# SerialKey.net
KiCad netlist of a schematic drawn in EAGLE
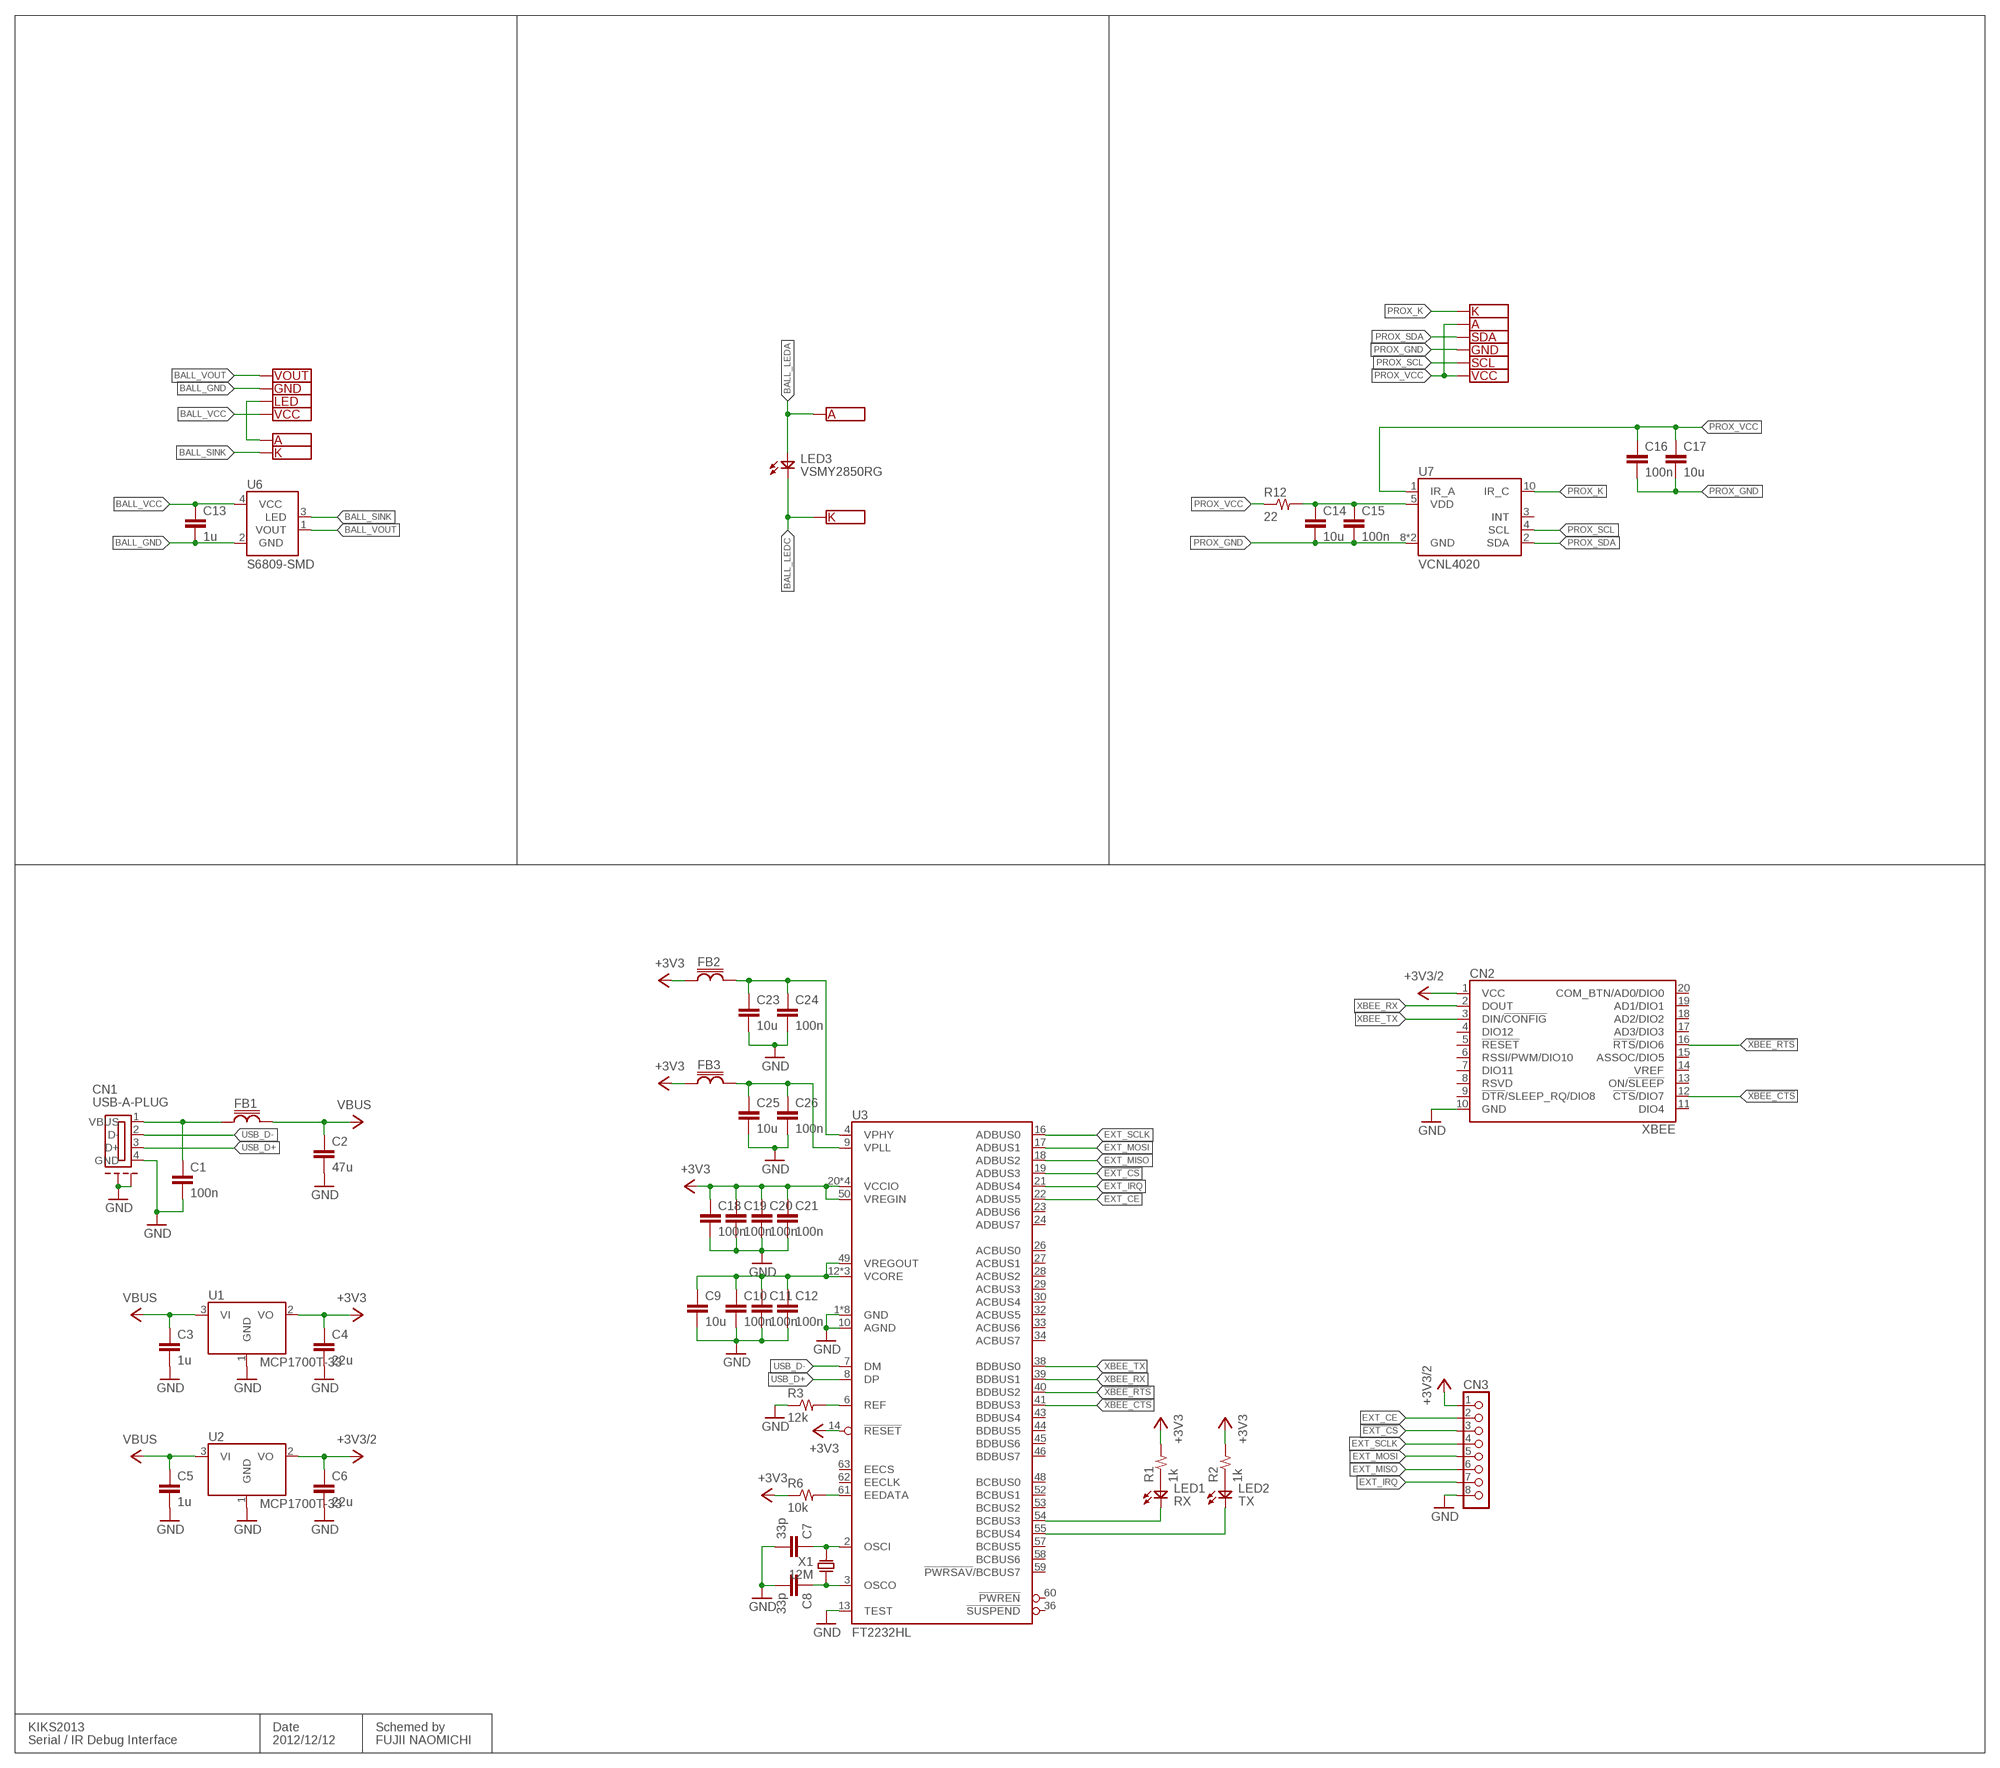
[diagram p0: schematic, sheet 1]

(export (version "E")
  (design (tool "Eeschema 10.0.6"))
  (components
    (comp (ref "C1")
      (value "100n")
      (footprint "eagle-import:1005")
      (libsource (lib "eagle-import") (part "C1005"))
    )
    (comp (ref "C2")
      (value "47u")
      (footprint "eagle-import:3216")
      (libsource (lib "eagle-import") (part "C3216"))
    )
    (comp (ref "C3")
      (value "1u")
      (footprint "eagle-import:1005")
      (libsource (lib "eagle-import") (part "C1005"))
    )
    (comp (ref "C4")
      (value "22u")
      (footprint "eagle-import:2012")
      (libsource (lib "eagle-import") (part "C2012"))
    )
    (comp (ref "C5")
      (value "1u")
      (footprint "eagle-import:1005")
      (libsource (lib "eagle-import") (part "C1005"))
    )
    (comp (ref "C6")
      (value "22u")
      (footprint "eagle-import:2012")
      (libsource (lib "eagle-import") (part "C2012"))
    )
    (comp (ref "C7")
      (value "33p")
      (footprint "eagle-import:1608")
      (libsource (lib "eagle-import") (part "C1608"))
    )
    (comp (ref "C8")
      (value "33p")
      (footprint "eagle-import:1608")
      (libsource (lib "eagle-import") (part "C1608"))
    )
    (comp (ref "C9")
      (value "10u")
      (footprint "eagle-import:1608")
      (libsource (lib "eagle-import") (part "C1608"))
    )
    (comp (ref "C10")
      (value "100n")
      (footprint "eagle-import:1005")
      (libsource (lib "eagle-import") (part "C1005"))
    )
    (comp (ref "C11")
      (value "100n")
      (footprint "eagle-import:1005")
      (libsource (lib "eagle-import") (part "C1005"))
    )
    (comp (ref "C12")
      (value "100n")
      (footprint "eagle-import:1005")
      (libsource (lib "eagle-import") (part "C1005"))
    )
    (comp (ref "C13")
      (value "1u")
      (footprint "eagle-import:1005")
      (libsource (lib "eagle-import") (part "C1005"))
    )
    (comp (ref "C14")
      (value "10u")
      (footprint "eagle-import:1608")
      (libsource (lib "eagle-import") (part "C1608"))
    )
    (comp (ref "C15")
      (value "100n")
      (footprint "eagle-import:1005")
      (libsource (lib "eagle-import") (part "C1005"))
    )
    (comp (ref "C16")
      (value "100n")
      (footprint "eagle-import:1005")
      (libsource (lib "eagle-import") (part "C1005"))
    )
    (comp (ref "C17")
      (value "10u")
      (footprint "eagle-import:1608")
      (libsource (lib "eagle-import") (part "C1608"))
    )
    (comp (ref "C18")
      (value "100n")
      (footprint "eagle-import:1005")
      (libsource (lib "eagle-import") (part "C1005"))
    )
    (comp (ref "C19")
      (value "100n")
      (footprint "eagle-import:1005")
      (libsource (lib "eagle-import") (part "C1005"))
    )
    (comp (ref "C20")
      (value "100n")
      (footprint "eagle-import:1005")
      (libsource (lib "eagle-import") (part "C1005"))
    )
    (comp (ref "C21")
      (value "100n")
      (footprint "eagle-import:1005")
      (libsource (lib "eagle-import") (part "C1005"))
    )
    (comp (ref "C23")
      (value "10u")
      (footprint "eagle-import:1608")
      (libsource (lib "eagle-import") (part "C1608"))
    )
    (comp (ref "C24")
      (value "100n")
      (footprint "eagle-import:1005")
      (libsource (lib "eagle-import") (part "C1005"))
    )
    (comp (ref "C25")
      (value "10u")
      (footprint "eagle-import:1608")
      (libsource (lib "eagle-import") (part "C1608"))
    )
    (comp (ref "C26")
      (value "100n")
      (footprint "eagle-import:1005")
      (libsource (lib "eagle-import") (part "C1005"))
    )
    (comp (ref "CN1")
      (value "USB-A-PLUG")
      (footprint "eagle-import:USB-A-PLUG")
      (libsource (lib "eagle-import") (part "USB-A-PLUG"))
    )
    (comp (ref "CN2")
      (value "XBEE")
      (footprint "eagle-import:XBEE-TH-NOSILK")
      (libsource (lib "eagle-import") (part "XBEE-TH-NOSILK"))
    )
    (comp (ref "CN3")
      (value "PIN1X8")
      (footprint "eagle-import:PIN1X8")
      (libsource (lib "eagle-import") (part "PIN1X8"))
    )
    (comp (ref "FB1")
      (value "FB1608")
      (footprint "eagle-import:1608")
      (libsource (lib "eagle-import") (part "FB1608"))
    )
    (comp (ref "FB2")
      (value "FB1608")
      (footprint "eagle-import:1608")
      (libsource (lib "eagle-import") (part "FB1608"))
    )
    (comp (ref "FB3")
      (value "FB1608")
      (footprint "eagle-import:1608")
      (libsource (lib "eagle-import") (part "FB1608"))
    )
    (comp (ref "LED1")
      (value "RX")
      (footprint "eagle-import:1608")
      (libsource (lib "eagle-import") (part "LED1608"))
    )
    (comp (ref "LED2")
      (value "TX")
      (footprint "eagle-import:1608")
      (libsource (lib "eagle-import") (part "LED1608"))
    )
    (comp (ref "LED3")
      (value "VSMY2850RG")
      (footprint "eagle-import:VISHAY-RGW")
      (libsource (lib "eagle-import") (part "VSMY2850RG"))
    )
    (comp (ref "R1")
      (value "1k")
      (footprint "eagle-import:1005")
      (libsource (lib "eagle-import") (part "R1005"))
    )
    (comp (ref "R2")
      (value "1k")
      (footprint "eagle-import:1005")
      (libsource (lib "eagle-import") (part "R1005"))
    )
    (comp (ref "R3")
      (value "12k")
      (footprint "eagle-import:1608")
      (libsource (lib "eagle-import") (part "R1608"))
    )
    (comp (ref "R6")
      (value "10k")
      (footprint "eagle-import:1005")
      (libsource (lib "eagle-import") (part "R1005"))
    )
    (comp (ref "R12")
      (value "22")
      (footprint "eagle-import:1005")
      (libsource (lib "eagle-import") (part "R1005"))
    )
    (comp (ref "T1")
      (value "VOUT")
      (footprint "eagle-import:TERMINAL")
      (libsource (lib "eagle-import") (part "TERMINAL"))
    )
    (comp (ref "T2")
      (value "GND")
      (footprint "eagle-import:TERMINAL")
      (libsource (lib "eagle-import") (part "TERMINAL"))
    )
    (comp (ref "T3")
      (value "LED")
      (footprint "eagle-import:TERMINAL")
      (libsource (lib "eagle-import") (part "TERMINAL"))
    )
    (comp (ref "T4")
      (value "VCC")
      (footprint "eagle-import:TERMINAL")
      (libsource (lib "eagle-import") (part "TERMINAL"))
    )
    (comp (ref "T5")
      (value "A")
      (footprint "eagle-import:TERMINAL")
      (libsource (lib "eagle-import") (part "TERMINAL"))
    )
    (comp (ref "T6")
      (value "K")
      (footprint "eagle-import:TERMINAL")
      (libsource (lib "eagle-import") (part "TERMINAL"))
    )
    (comp (ref "T7")
      (value "A")
      (footprint "eagle-import:TERMINAL")
      (libsource (lib "eagle-import") (part "TERMINAL"))
    )
    (comp (ref "T8")
      (value "K")
      (footprint "eagle-import:TERMINAL")
      (libsource (lib "eagle-import") (part "TERMINAL"))
    )
    (comp (ref "T9")
      (value "SDA")
      (footprint "eagle-import:TERMINAL")
      (libsource (lib "eagle-import") (part "TERMINAL"))
    )
    (comp (ref "T10")
      (value "GND")
      (footprint "eagle-import:TERMINAL")
      (libsource (lib "eagle-import") (part "TERMINAL"))
    )
    (comp (ref "T11")
      (value "SCL")
      (footprint "eagle-import:TERMINAL")
      (libsource (lib "eagle-import") (part "TERMINAL"))
    )
    (comp (ref "T12")
      (value "VCC")
      (footprint "eagle-import:TERMINAL")
      (libsource (lib "eagle-import") (part "TERMINAL"))
    )
    (comp (ref "T13")
      (value "A")
      (footprint "eagle-import:TERMINAL")
      (libsource (lib "eagle-import") (part "TERMINAL"))
    )
    (comp (ref "T14")
      (value "K")
      (footprint "eagle-import:TERMINAL")
      (libsource (lib "eagle-import") (part "TERMINAL"))
    )
    (comp (ref "U1")
      (value "MCP1700T-33")
      (footprint "eagle-import:SOT23-3")
      (libsource (lib "eagle-import") (part "MCP1700T-33"))
    )
    (comp (ref "U2")
      (value "MCP1700T-33")
      (footprint "eagle-import:SOT23-3")
      (libsource (lib "eagle-import") (part "MCP1700T-33"))
    )
    (comp (ref "U3")
      (value "FT2232HL")
      (footprint "eagle-import:QFP64-0.5")
      (libsource (lib "eagle-import") (part "FT2232HL"))
    )
    (comp (ref "U6")
      (value "S6809-SMD")
      (footprint "eagle-import:S6809")
      (libsource (lib "eagle-import") (part "S6809-SMD"))
    )
    (comp (ref "U7")
      (value "VCNL4020")
      (footprint "eagle-import:VCNL4020")
      (libsource (lib "eagle-import") (part "VCNL4020"))
    )
    (comp (ref "X1")
      (value "12M")
      (footprint "eagle-import:HC49")
      (libsource (lib "eagle-import") (part "HC49"))
    )
  )
  (nets
    (net (code "1") (name "+3V3") (class "Default")
      (node (ref "C18") (pin "1") (pinfunction "1_1") (pintype "passive"))
      (node (ref "C19") (pin "1") (pinfunction "1_1") (pintype "passive"))
      (node (ref "C20") (pin "1") (pinfunction "1_1") (pintype "passive"))
      (node (ref "C21") (pin "1") (pinfunction "1_1") (pintype "passive"))
      (node (ref "C4") (pin "1") (pinfunction "1_1") (pintype "passive"))
      (node (ref "FB2") (pin "1") (pinfunction "1_1") (pintype "passive"))
      (node (ref "FB3") (pin "1") (pinfunction "1_1") (pintype "passive"))
      (node (ref "R1") (pin "2") (pinfunction "2_2") (pintype "passive"))
      (node (ref "R2") (pin "2") (pinfunction "2_2") (pintype "passive"))
      (node (ref "R6") (pin "1") (pinfunction "1_1") (pintype "passive"))
      (node (ref "U1") (pin "2") (pinfunction "VO_2") (pintype "bidirectional"))
      (node (ref "U3") (pin "14") (pinfunction "~{RESET}_14") (pintype "bidirectional"))
      (node (ref "U3") (pin "20") (pinfunction "VCCIO_20") (pintype "bidirectional"))
      (node (ref "U3") (pin "31") (pinfunction "VCCIO_31") (pintype "bidirectional"))
      (node (ref "U3") (pin "42") (pinfunction "VCCIO_42") (pintype "bidirectional"))
      (node (ref "U3") (pin "50") (pinfunction "VREGIN_50") (pintype "bidirectional"))
      (node (ref "U3") (pin "56") (pinfunction "VCCIO_56") (pintype "bidirectional"))
    )
    (net (code "2") (name "+3V3{slash}2") (class "Default")
      (node (ref "C6") (pin "1") (pinfunction "1_1") (pintype "passive"))
      (node (ref "CN2") (pin "1") (pinfunction "VCC_1") (pintype "bidirectional"))
      (node (ref "CN3") (pin "1") (pinfunction "1_1") (pintype "passive"))
      (node (ref "U2") (pin "2") (pinfunction "VO_2") (pintype "bidirectional"))
    )
    (net (code "3") (name "/~{EXT_CS}") (class "Default")
      (node (ref "CN3") (pin "3") (pinfunction "3_3") (pintype "passive"))
      (node (ref "U3") (pin "19") (pinfunction "ADBUS3_19") (pintype "bidirectional"))
    )
    (net (code "4") (name "/~{XBEE_CTS}") (class "Default")
      (node (ref "CN2") (pin "12") (pinfunction "~{CTS}/DIO7_12") (pintype "bidirectional"))
      (node (ref "U3") (pin "41") (pinfunction "BDBUS3_41") (pintype "bidirectional"))
    )
    (net (code "5") (name "/~{XBEE_RTS}") (class "Default")
      (node (ref "CN2") (pin "16") (pinfunction "~{RTS}/DIO6_16") (pintype "bidirectional"))
      (node (ref "U3") (pin "40") (pinfunction "BDBUS2_40") (pintype "bidirectional"))
    )
    (net (code "6") (name "BALL_GND") (class "Default")
      (node (ref "C13") (pin "2") (pinfunction "2_2") (pintype "passive"))
      (node (ref "T2") (pin "1") (pinfunction "1_1") (pintype "passive"))
      (node (ref "U6") (pin "2") (pinfunction "GND_2") (pintype "bidirectional"))
    )
    (net (code "7") (name "BALL_LEDA") (class "Default")
      (node (ref "LED3") (pin "A") (pinfunction "A_A") (pintype "passive"))
      (node (ref "T7") (pin "1") (pinfunction "1_1") (pintype "passive"))
    )
    (net (code "8") (name "BALL_LEDC") (class "Default")
      (node (ref "LED3") (pin "K") (pinfunction "K_K") (pintype "passive"))
      (node (ref "T8") (pin "1") (pinfunction "1_1") (pintype "passive"))
    )
    (net (code "9") (name "BALL_SINK") (class "Default")
      (node (ref "T6") (pin "1") (pinfunction "1_1") (pintype "passive"))
      (node (ref "U6") (pin "3") (pinfunction "LED_3") (pintype "bidirectional"))
    )
    (net (code "10") (name "BALL_VCC") (class "Default")
      (node (ref "C13") (pin "1") (pinfunction "1_1") (pintype "passive"))
      (node (ref "T4") (pin "1") (pinfunction "1_1") (pintype "passive"))
      (node (ref "U6") (pin "4") (pinfunction "VCC_4") (pintype "bidirectional"))
    )
    (net (code "11") (name "BALL_VOUT") (class "Default")
      (node (ref "T1") (pin "1") (pinfunction "1_1") (pintype "passive"))
      (node (ref "U6") (pin "1") (pinfunction "VOUT_1") (pintype "bidirectional"))
    )
    (net (code "12") (name "EXT_CE") (class "Default")
      (node (ref "CN3") (pin "2") (pinfunction "2_2") (pintype "passive"))
      (node (ref "U3") (pin "22") (pinfunction "ADBUS5_22") (pintype "bidirectional"))
    )
    (net (code "13") (name "EXT_IRQ") (class "Default")
      (node (ref "CN3") (pin "7") (pinfunction "7_7") (pintype "passive"))
      (node (ref "U3") (pin "21") (pinfunction "ADBUS4_21") (pintype "bidirectional"))
    )
    (net (code "14") (name "EXT_MISO") (class "Default")
      (node (ref "CN3") (pin "6") (pinfunction "6_6") (pintype "passive"))
      (node (ref "U3") (pin "18") (pinfunction "ADBUS2_18") (pintype "bidirectional"))
    )
    (net (code "15") (name "EXT_MOSI") (class "Default")
      (node (ref "CN3") (pin "5") (pinfunction "5_5") (pintype "passive"))
      (node (ref "U3") (pin "17") (pinfunction "ADBUS1_17") (pintype "bidirectional"))
    )
    (net (code "16") (name "EXT_SCLK") (class "Default")
      (node (ref "CN3") (pin "4") (pinfunction "4_4") (pintype "passive"))
      (node (ref "U3") (pin "16") (pinfunction "ADBUS0_16") (pintype "bidirectional"))
    )
    (net (code "17") (name "GND") (class "Default")
      (node (ref "C1") (pin "2") (pinfunction "2_2") (pintype "passive"))
      (node (ref "C10") (pin "2") (pinfunction "2_2") (pintype "passive"))
      (node (ref "C11") (pin "2") (pinfunction "2_2") (pintype "passive"))
      (node (ref "C12") (pin "2") (pinfunction "2_2") (pintype "passive"))
      (node (ref "C18") (pin "2") (pinfunction "2_2") (pintype "passive"))
      (node (ref "C19") (pin "2") (pinfunction "2_2") (pintype "passive"))
      (node (ref "C2") (pin "2") (pinfunction "2_2") (pintype "passive"))
      (node (ref "C20") (pin "2") (pinfunction "2_2") (pintype "passive"))
      (node (ref "C21") (pin "2") (pinfunction "2_2") (pintype "passive"))
      (node (ref "C23") (pin "2") (pinfunction "2_2") (pintype "passive"))
      (node (ref "C24") (pin "2") (pinfunction "2_2") (pintype "passive"))
      (node (ref "C25") (pin "2") (pinfunction "2_2") (pintype "passive"))
      (node (ref "C26") (pin "2") (pinfunction "2_2") (pintype "passive"))
      (node (ref "C3") (pin "2") (pinfunction "2_2") (pintype "passive"))
      (node (ref "C4") (pin "2") (pinfunction "2_2") (pintype "passive"))
      (node (ref "C5") (pin "2") (pinfunction "2_2") (pintype "passive"))
      (node (ref "C6") (pin "2") (pinfunction "2_2") (pintype "passive"))
      (node (ref "C7") (pin "2") (pinfunction "2_2") (pintype "passive"))
      (node (ref "C8") (pin "2") (pinfunction "2_2") (pintype "passive"))
      (node (ref "C9") (pin "2") (pinfunction "2_2") (pintype "passive"))
      (node (ref "CN1") (pin "4") (pinfunction "GND_4") (pintype "passive"))
      (node (ref "CN1") (pin "S1") (pinfunction "S1_S1") (pintype "passive"))
      (node (ref "CN1") (pin "S2") (pinfunction "S2_S2") (pintype "passive"))
      (node (ref "CN2") (pin "10") (pinfunction "GND_10") (pintype "bidirectional"))
      (node (ref "CN3") (pin "8") (pinfunction "8_8") (pintype "passive"))
      (node (ref "R3") (pin "1") (pinfunction "1_1") (pintype "passive"))
      (node (ref "U1") (pin "1") (pinfunction "GND_1") (pintype "bidirectional"))
      (node (ref "U2") (pin "1") (pinfunction "GND_1") (pintype "bidirectional"))
      (node (ref "U3") (pin "1") (pinfunction "GND_1") (pintype "bidirectional"))
      (node (ref "U3") (pin "10") (pinfunction "AGND_10") (pintype "bidirectional"))
      (node (ref "U3") (pin "11") (pinfunction "GND_11") (pintype "bidirectional"))
      (node (ref "U3") (pin "13") (pinfunction "TEST_13") (pintype "bidirectional"))
      (node (ref "U3") (pin "15") (pinfunction "GND_15") (pintype "bidirectional"))
      (node (ref "U3") (pin "25") (pinfunction "GND_25") (pintype "bidirectional"))
      (node (ref "U3") (pin "35") (pinfunction "GND_35") (pintype "bidirectional"))
      (node (ref "U3") (pin "47") (pinfunction "GND_47") (pintype "bidirectional"))
      (node (ref "U3") (pin "5") (pinfunction "GND_5") (pintype "bidirectional"))
      (node (ref "U3") (pin "51") (pinfunction "GND_51") (pintype "bidirectional"))
    )
    (net (code "18") (name "Net-(CN1-VBUS)") (class "Default")
      (node (ref "C1") (pin "1") (pinfunction "1_1") (pintype "passive"))
      (node (ref "CN1") (pin "1") (pinfunction "VBUS_1") (pintype "passive"))
      (node (ref "FB1") (pin "1") (pinfunction "1_1") (pintype "passive"))
    )
    (net (code "19") (name "Net-(LED1-PadA)") (class "Default")
      (node (ref "LED1") (pin "A") (pinfunction "A_A") (pintype "passive"))
      (node (ref "R1") (pin "1") (pinfunction "1_1") (pintype "passive"))
    )
    (net (code "20") (name "Net-(LED2-PadA)") (class "Default")
      (node (ref "LED2") (pin "A") (pinfunction "A_A") (pintype "passive"))
      (node (ref "R2") (pin "1") (pinfunction "1_1") (pintype "passive"))
    )
    (net (code "21") (name "Net-(T3-Pad1)") (class "Default")
      (node (ref "T3") (pin "1") (pinfunction "1_1") (pintype "passive"))
      (node (ref "T5") (pin "1") (pinfunction "1_1") (pintype "passive"))
    )
    (net (code "22") (name "Net-(U3-BCBUS3)") (class "Default")
      (node (ref "LED1") (pin "K") (pinfunction "K_K") (pintype "passive"))
      (node (ref "U3") (pin "54") (pinfunction "BCBUS3_54") (pintype "bidirectional"))
    )
    (net (code "23") (name "Net-(U3-BCBUS4)") (class "Default")
      (node (ref "LED2") (pin "K") (pinfunction "K_K") (pintype "passive"))
      (node (ref "U3") (pin "55") (pinfunction "BCBUS4_55") (pintype "bidirectional"))
    )
    (net (code "24") (name "Net-(U3-EEDATA)") (class "Default")
      (node (ref "R6") (pin "2") (pinfunction "2_2") (pintype "passive"))
      (node (ref "U3") (pin "61") (pinfunction "EEDATA_61") (pintype "bidirectional"))
    )
    (net (code "25") (name "Net-(U3-OSCI)") (class "Default")
      (node (ref "C7") (pin "1") (pinfunction "1_1") (pintype "passive"))
      (node (ref "U3") (pin "2") (pinfunction "OSCI_2") (pintype "bidirectional"))
      (node (ref "X1") (pin "1") (pinfunction "A_1") (pintype "passive"))
    )
    (net (code "26") (name "Net-(U3-OSCO)") (class "Default")
      (node (ref "C8") (pin "1") (pinfunction "1_1") (pintype "passive"))
      (node (ref "U3") (pin "3") (pinfunction "OSCO_3") (pintype "bidirectional"))
      (node (ref "X1") (pin "2") (pinfunction "B_2") (pintype "passive"))
    )
    (net (code "27") (name "Net-(U3-REF)") (class "Default")
      (node (ref "R3") (pin "2") (pinfunction "2_2") (pintype "passive"))
      (node (ref "U3") (pin "6") (pinfunction "REF_6") (pintype "bidirectional"))
    )
    (net (code "28") (name "Net-(U3-VPHY)") (class "Default")
      (node (ref "C23") (pin "1") (pinfunction "1_1") (pintype "passive"))
      (node (ref "C24") (pin "1") (pinfunction "1_1") (pintype "passive"))
      (node (ref "FB2") (pin "2") (pinfunction "2_2") (pintype "passive"))
      (node (ref "U3") (pin "4") (pinfunction "VPHY_4") (pintype "bidirectional"))
    )
    (net (code "29") (name "Net-(U3-VPLL)") (class "Default")
      (node (ref "C25") (pin "1") (pinfunction "1_1") (pintype "passive"))
      (node (ref "C26") (pin "1") (pinfunction "1_1") (pintype "passive"))
      (node (ref "FB3") (pin "2") (pinfunction "2_2") (pintype "passive"))
      (node (ref "U3") (pin "9") (pinfunction "VPLL_9") (pintype "bidirectional"))
    )
    (net (code "30") (name "Net-(U3-VREGOUT)") (class "Default")
      (node (ref "C10") (pin "1") (pinfunction "1_1") (pintype "passive"))
      (node (ref "C11") (pin "1") (pinfunction "1_1") (pintype "passive"))
      (node (ref "C12") (pin "1") (pinfunction "1_1") (pintype "passive"))
      (node (ref "C9") (pin "1") (pinfunction "1_1") (pintype "passive"))
      (node (ref "U3") (pin "12") (pinfunction "VCORE_12") (pintype "bidirectional"))
      (node (ref "U3") (pin "37") (pinfunction "VCORE_37") (pintype "bidirectional"))
      (node (ref "U3") (pin "49") (pinfunction "VREGOUT_49") (pintype "bidirectional"))
      (node (ref "U3") (pin "64") (pinfunction "VCORE_64") (pintype "bidirectional"))
    )
    (net (code "31") (name "Net-(U7-VDD)") (class "Default")
      (node (ref "C14") (pin "1") (pinfunction "1_1") (pintype "passive"))
      (node (ref "C15") (pin "1") (pinfunction "1_1") (pintype "passive"))
      (node (ref "R12") (pin "2") (pinfunction "2_2") (pintype "passive"))
      (node (ref "U7") (pin "5") (pinfunction "VDD_5") (pintype "bidirectional"))
    )
    (net (code "32") (name "PROX_GND") (class "Default")
      (node (ref "C14") (pin "2") (pinfunction "2_2") (pintype "passive"))
      (node (ref "C15") (pin "2") (pinfunction "2_2") (pintype "passive"))
      (node (ref "C16") (pin "2") (pinfunction "2_2") (pintype "passive"))
      (node (ref "C17") (pin "2") (pinfunction "2_2") (pintype "passive"))
      (node (ref "T10") (pin "1") (pinfunction "1_1") (pintype "passive"))
      (node (ref "U7") (pin "8") (pinfunction "GND_8") (pintype "bidirectional"))
      (node (ref "U7") (pin "9") (pinfunction "GND_9") (pintype "bidirectional"))
    )
    (net (code "33") (name "PROX_K") (class "Default")
      (node (ref "T14") (pin "1") (pinfunction "1_1") (pintype "passive"))
      (node (ref "U7") (pin "10") (pinfunction "IR_C_10") (pintype "bidirectional"))
    )
    (net (code "34") (name "PROX_SCL") (class "Default")
      (node (ref "T11") (pin "1") (pinfunction "1_1") (pintype "passive"))
      (node (ref "U7") (pin "4") (pinfunction "SCL_4") (pintype "bidirectional"))
    )
    (net (code "35") (name "PROX_SDA") (class "Default")
      (node (ref "T9") (pin "1") (pinfunction "1_1") (pintype "passive"))
      (node (ref "U7") (pin "2") (pinfunction "SDA_2") (pintype "bidirectional"))
    )
    (net (code "36") (name "PROX_VCC") (class "Default")
      (node (ref "C16") (pin "1") (pinfunction "1_1") (pintype "passive"))
      (node (ref "C17") (pin "1") (pinfunction "1_1") (pintype "passive"))
      (node (ref "R12") (pin "1") (pinfunction "1_1") (pintype "passive"))
      (node (ref "T12") (pin "1") (pinfunction "1_1") (pintype "passive"))
      (node (ref "T13") (pin "1") (pinfunction "1_1") (pintype "passive"))
      (node (ref "U7") (pin "1") (pinfunction "IR_A_1") (pintype "bidirectional"))
    )
    (net (code "37") (name "USB_D+") (class "Default")
      (node (ref "CN1") (pin "3") (pinfunction "D+_3") (pintype "passive"))
      (node (ref "U3") (pin "8") (pinfunction "DP_8") (pintype "bidirectional"))
    )
    (net (code "38") (name "USB_D-") (class "Default")
      (node (ref "CN1") (pin "2") (pinfunction "D-_2") (pintype "passive"))
      (node (ref "U3") (pin "7") (pinfunction "DM_7") (pintype "bidirectional"))
    )
    (net (code "39") (name "VBUS") (class "Default")
      (node (ref "C2") (pin "1") (pinfunction "1_1") (pintype "passive"))
      (node (ref "C3") (pin "1") (pinfunction "1_1") (pintype "passive"))
      (node (ref "C5") (pin "1") (pinfunction "1_1") (pintype "passive"))
      (node (ref "FB1") (pin "2") (pinfunction "2_2") (pintype "passive"))
      (node (ref "U1") (pin "3") (pinfunction "VI_3") (pintype "bidirectional"))
      (node (ref "U2") (pin "3") (pinfunction "VI_3") (pintype "bidirectional"))
    )
    (net (code "40") (name "XBEE_RX") (class "Default")
      (node (ref "CN2") (pin "2") (pinfunction "DOUT_2") (pintype "bidirectional"))
      (node (ref "U3") (pin "39") (pinfunction "BDBUS1_39") (pintype "bidirectional"))
    )
    (net (code "41") (name "XBEE_TX") (class "Default")
      (node (ref "CN2") (pin "3") (pinfunction "DIN/~{CONFIG}_3") (pintype "bidirectional"))
      (node (ref "U3") (pin "38") (pinfunction "BDBUS0_38") (pintype "bidirectional"))
    )
    (net (code "42") (name "unconnected-(CN2-AD1{slash}DIO1-Pad19)") (class "Default")
      (node (ref "CN2") (pin "19") (pinfunction "AD1/DIO1_19") (pintype "bidirectional"))
    )
    (net (code "43") (name "unconnected-(CN2-AD2{slash}DIO2-Pad18)") (class "Default")
      (node (ref "CN2") (pin "18") (pinfunction "AD2/DIO2_18") (pintype "bidirectional"))
    )
    (net (code "44") (name "unconnected-(CN2-AD3{slash}DIO3-Pad17)") (class "Default")
      (node (ref "CN2") (pin "17") (pinfunction "AD3/DIO3_17") (pintype "bidirectional"))
    )
    (net (code "45") (name "unconnected-(CN2-ASSOC{slash}DIO5-Pad15)") (class "Default")
      (node (ref "CN2") (pin "15") (pinfunction "ASSOC/DIO5_15") (pintype "bidirectional"))
    )
    (net (code "46") (name "unconnected-(CN2-COM_BTN{slash}AD0{slash}DIO0-Pad20)") (class "Default")
      (node (ref "CN2") (pin "20") (pinfunction "COM_BTN/AD0/DIO0_20") (pintype "bidirectional"))
    )
    (net (code "47") (name "unconnected-(CN2-DIO4-Pad11)") (class "Default")
      (node (ref "CN2") (pin "11") (pinfunction "DIO4_11") (pintype "bidirectional"))
    )
    (net (code "48") (name "unconnected-(CN2-DIO11-Pad7)") (class "Default")
      (node (ref "CN2") (pin "7") (pinfunction "DIO11_7") (pintype "bidirectional"))
    )
    (net (code "49") (name "unconnected-(CN2-DIO12-Pad4)") (class "Default")
      (node (ref "CN2") (pin "4") (pinfunction "DIO12_4") (pintype "bidirectional"))
    )
    (net (code "50") (name "unconnected-(CN2-ON{slash}~{SLEEP}-Pad13)") (class "Default")
      (node (ref "CN2") (pin "13") (pinfunction "ON/~{SLEEP}_13") (pintype "bidirectional"))
    )
    (net (code "51") (name "unconnected-(CN2-RSSI{slash}PWM{slash}DIO10-Pad6)") (class "Default")
      (node (ref "CN2") (pin "6") (pinfunction "RSSI/PWM/DIO10_6") (pintype "bidirectional"))
    )
    (net (code "52") (name "unconnected-(CN2-RSVD-Pad8)") (class "Default")
      (node (ref "CN2") (pin "8") (pinfunction "RSVD_8") (pintype "bidirectional"))
    )
    (net (code "53") (name "unconnected-(CN2-VREF-Pad14)") (class "Default")
      (node (ref "CN2") (pin "14") (pinfunction "VREF_14") (pintype "bidirectional"))
    )
    (net (code "54") (name "unconnected-(CN2-~{DTR}{slash}SLEEP_RQ{slash}DIO8-Pad9)") (class "Default")
      (node (ref "CN2") (pin "9") (pinfunction "~{DTR}/SLEEP_RQ/DIO8_9") (pintype "bidirectional"))
    )
    (net (code "55") (name "unconnected-(CN2-~{RESET}-Pad5)") (class "Default")
      (node (ref "CN2") (pin "5") (pinfunction "~{RESET}_5") (pintype "bidirectional"))
    )
    (net (code "56") (name "unconnected-(U3-ACBUS0-Pad26)") (class "Default")
      (node (ref "U3") (pin "26") (pinfunction "ACBUS0_26") (pintype "bidirectional"))
    )
    (net (code "57") (name "unconnected-(U3-ACBUS1-Pad27)") (class "Default")
      (node (ref "U3") (pin "27") (pinfunction "ACBUS1_27") (pintype "bidirectional"))
    )
    (net (code "58") (name "unconnected-(U3-ACBUS2-Pad28)") (class "Default")
      (node (ref "U3") (pin "28") (pinfunction "ACBUS2_28") (pintype "bidirectional"))
    )
    (net (code "59") (name "unconnected-(U3-ACBUS3-Pad29)") (class "Default")
      (node (ref "U3") (pin "29") (pinfunction "ACBUS3_29") (pintype "bidirectional"))
    )
    (net (code "60") (name "unconnected-(U3-ACBUS4-Pad30)") (class "Default")
      (node (ref "U3") (pin "30") (pinfunction "ACBUS4_30") (pintype "bidirectional"))
    )
    (net (code "61") (name "unconnected-(U3-ACBUS5-Pad32)") (class "Default")
      (node (ref "U3") (pin "32") (pinfunction "ACBUS5_32") (pintype "bidirectional"))
    )
    (net (code "62") (name "unconnected-(U3-ACBUS6-Pad33)") (class "Default")
      (node (ref "U3") (pin "33") (pinfunction "ACBUS6_33") (pintype "bidirectional"))
    )
    (net (code "63") (name "unconnected-(U3-ACBUS7-Pad34)") (class "Default")
      (node (ref "U3") (pin "34") (pinfunction "ACBUS7_34") (pintype "bidirectional"))
    )
    (net (code "64") (name "unconnected-(U3-ADBUS6-Pad23)") (class "Default")
      (node (ref "U3") (pin "23") (pinfunction "ADBUS6_23") (pintype "bidirectional"))
    )
    (net (code "65") (name "unconnected-(U3-ADBUS7-Pad24)") (class "Default")
      (node (ref "U3") (pin "24") (pinfunction "ADBUS7_24") (pintype "bidirectional"))
    )
    (net (code "66") (name "unconnected-(U3-BCBUS0-Pad48)") (class "Default")
      (node (ref "U3") (pin "48") (pinfunction "BCBUS0_48") (pintype "bidirectional"))
    )
    (net (code "67") (name "unconnected-(U3-BCBUS1-Pad52)") (class "Default")
      (node (ref "U3") (pin "52") (pinfunction "BCBUS1_52") (pintype "bidirectional"))
    )
    (net (code "68") (name "unconnected-(U3-BCBUS2-Pad53)") (class "Default")
      (node (ref "U3") (pin "53") (pinfunction "BCBUS2_53") (pintype "bidirectional"))
    )
    (net (code "69") (name "unconnected-(U3-BCBUS5-Pad57)") (class "Default")
      (node (ref "U3") (pin "57") (pinfunction "BCBUS5_57") (pintype "bidirectional"))
    )
    (net (code "70") (name "unconnected-(U3-BCBUS6-Pad58)") (class "Default")
      (node (ref "U3") (pin "58") (pinfunction "BCBUS6_58") (pintype "bidirectional"))
    )
    (net (code "71") (name "unconnected-(U3-BDBUS4-Pad43)") (class "Default")
      (node (ref "U3") (pin "43") (pinfunction "BDBUS4_43") (pintype "bidirectional"))
    )
    (net (code "72") (name "unconnected-(U3-BDBUS5-Pad44)") (class "Default")
      (node (ref "U3") (pin "44") (pinfunction "BDBUS5_44") (pintype "bidirectional"))
    )
    (net (code "73") (name "unconnected-(U3-BDBUS6-Pad45)") (class "Default")
      (node (ref "U3") (pin "45") (pinfunction "BDBUS6_45") (pintype "bidirectional"))
    )
    (net (code "74") (name "unconnected-(U3-BDBUS7-Pad46)") (class "Default")
      (node (ref "U3") (pin "46") (pinfunction "BDBUS7_46") (pintype "bidirectional"))
    )
    (net (code "75") (name "unconnected-(U3-EECLK-Pad62)") (class "Default")
      (node (ref "U3") (pin "62") (pinfunction "EECLK_62") (pintype "bidirectional"))
    )
    (net (code "76") (name "unconnected-(U3-EECS-Pad63)") (class "Default")
      (node (ref "U3") (pin "63") (pinfunction "EECS_63") (pintype "bidirectional"))
    )
    (net (code "77") (name "unconnected-(U3-~{PWREN}-Pad60)") (class "Default")
      (node (ref "U3") (pin "60") (pinfunction "~{PWREN}_60") (pintype "bidirectional"))
    )
    (net (code "78") (name "unconnected-(U3-~{PWRSAV}{slash}BCBUS7-Pad59)") (class "Default")
      (node (ref "U3") (pin "59") (pinfunction "~{PWRSAV}/BCBUS7_59") (pintype "bidirectional"))
    )
    (net (code "79") (name "unconnected-(U3-~{SUSPEND}-Pad36)") (class "Default")
      (node (ref "U3") (pin "36") (pinfunction "~{SUSPEND}_36") (pintype "bidirectional"))
    )
    (net (code "80") (name "unconnected-(U7-INT-Pad3)") (class "Default")
      (node (ref "U7") (pin "3") (pinfunction "INT_3") (pintype "bidirectional"))
    )
  )
)
